# Galaksija_keyboard_matrix.net
KiCad netlist of a schematic drawn in EAGLE
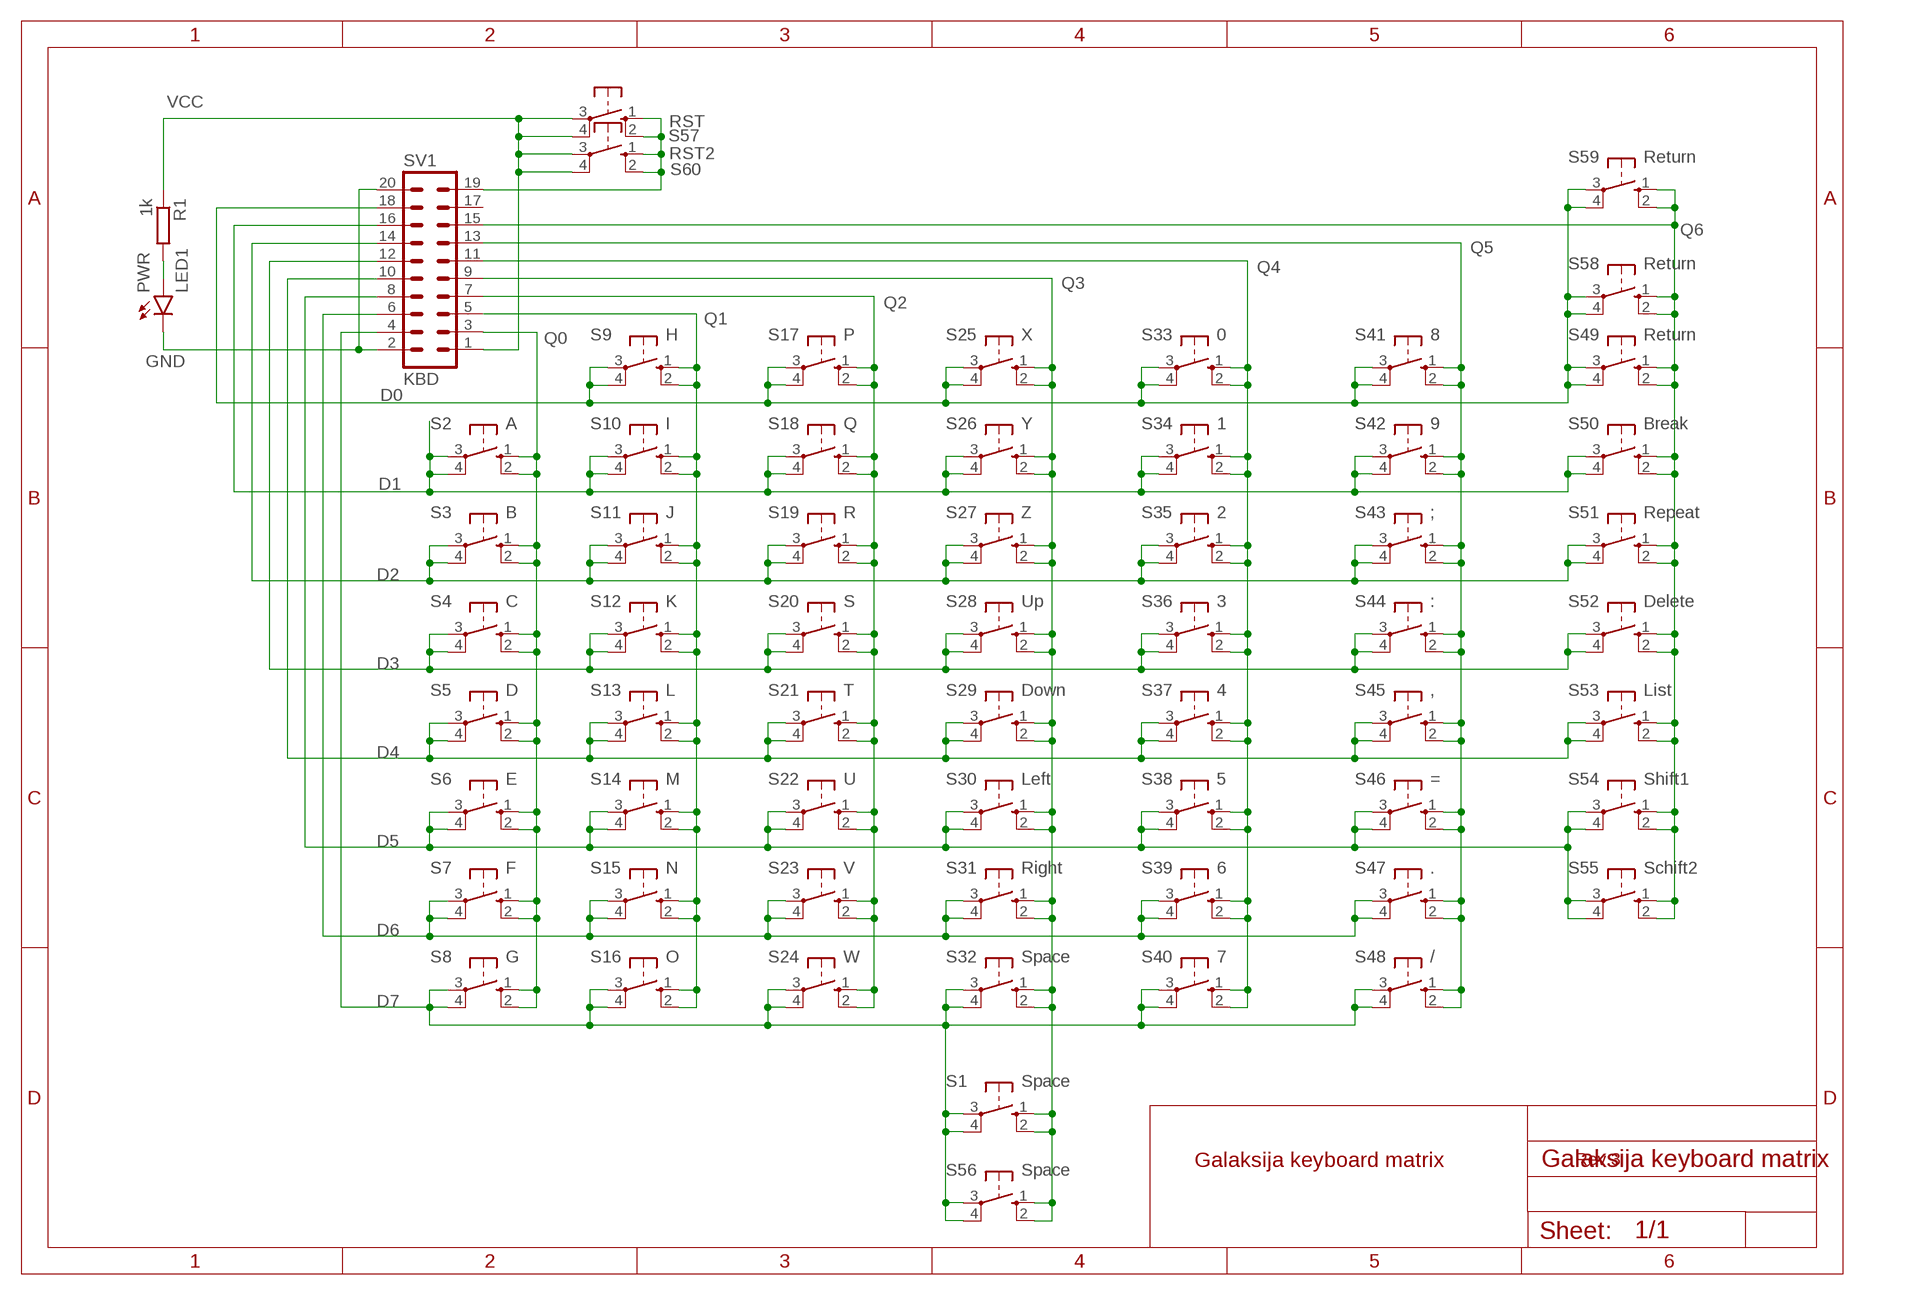
[diagram p0: schematic, sheet 1]

(export (version "E")
  (design (tool "Eeschema 10.0.6"))
  (components
    (comp (ref "LED1")
      (value "PWR")
      (footprint "eagle-import:LED5MM")
      (libsource (lib "eagle-import") (part "LED5MM"))
    )
    (comp (ref "R1")
      (value "1k")
      (footprint "eagle-import:0207_10")
      (libsource (lib "eagle-import") (part "R-EU_0207/10"))
    )
    (comp (ref "S1")
      (value "Space")
      (footprint "eagle-import:B3F-40XX")
      (fields (field (name "MF") "OMRON COMPONENTS USA") (field (name "MPN") "B3F-4000"))
      (libsource (lib "eagle-import") (part "40-XX"))
    )
    (comp (ref "S2")
      (value "A")
      (footprint "eagle-import:B3F-40XX")
      (fields (field (name "MF") "OMRON COMPONENTS USA") (field (name "MPN") "B3F-4000"))
      (libsource (lib "eagle-import") (part "40-XX"))
    )
    (comp (ref "S3")
      (value "B")
      (footprint "eagle-import:B3F-40XX")
      (fields (field (name "MF") "OMRON COMPONENTS USA") (field (name "MPN") "B3F-4000"))
      (libsource (lib "eagle-import") (part "40-XX"))
    )
    (comp (ref "S4")
      (value "C")
      (footprint "eagle-import:B3F-40XX")
      (fields (field (name "MF") "OMRON COMPONENTS USA") (field (name "MPN") "B3F-4000"))
      (libsource (lib "eagle-import") (part "40-XX"))
    )
    (comp (ref "S5")
      (value "D")
      (footprint "eagle-import:B3F-40XX")
      (fields (field (name "MF") "OMRON COMPONENTS USA") (field (name "MPN") "B3F-4000"))
      (libsource (lib "eagle-import") (part "40-XX"))
    )
    (comp (ref "S6")
      (value "E")
      (footprint "eagle-import:B3F-40XX")
      (fields (field (name "MF") "OMRON COMPONENTS USA") (field (name "MPN") "B3F-4000"))
      (libsource (lib "eagle-import") (part "40-XX"))
    )
    (comp (ref "S7")
      (value "F")
      (footprint "eagle-import:B3F-40XX")
      (fields (field (name "MF") "OMRON COMPONENTS USA") (field (name "MPN") "B3F-4000"))
      (libsource (lib "eagle-import") (part "40-XX"))
    )
    (comp (ref "S8")
      (value "G")
      (footprint "eagle-import:B3F-40XX")
      (fields (field (name "MF") "OMRON COMPONENTS USA") (field (name "MPN") "B3F-4000"))
      (libsource (lib "eagle-import") (part "40-XX"))
    )
    (comp (ref "S9")
      (value "H")
      (footprint "eagle-import:B3F-40XX")
      (fields (field (name "MF") "OMRON COMPONENTS USA") (field (name "MPN") "B3F-4000"))
      (libsource (lib "eagle-import") (part "40-XX"))
    )
    (comp (ref "S10")
      (value "I")
      (footprint "eagle-import:B3F-40XX")
      (fields (field (name "MF") "OMRON COMPONENTS USA") (field (name "MPN") "B3F-4000"))
      (libsource (lib "eagle-import") (part "40-XX"))
    )
    (comp (ref "S11")
      (value "J")
      (footprint "eagle-import:B3F-40XX")
      (fields (field (name "MF") "OMRON COMPONENTS USA") (field (name "MPN") "B3F-4000"))
      (libsource (lib "eagle-import") (part "40-XX"))
    )
    (comp (ref "S12")
      (value "K")
      (footprint "eagle-import:B3F-40XX")
      (fields (field (name "MF") "OMRON COMPONENTS USA") (field (name "MPN") "B3F-4000"))
      (libsource (lib "eagle-import") (part "40-XX"))
    )
    (comp (ref "S13")
      (value "L")
      (footprint "eagle-import:B3F-40XX")
      (fields (field (name "MF") "OMRON COMPONENTS USA") (field (name "MPN") "B3F-4000"))
      (libsource (lib "eagle-import") (part "40-XX"))
    )
    (comp (ref "S14")
      (value "M")
      (footprint "eagle-import:B3F-40XX")
      (fields (field (name "MF") "OMRON COMPONENTS USA") (field (name "MPN") "B3F-4000"))
      (libsource (lib "eagle-import") (part "40-XX"))
    )
    (comp (ref "S15")
      (value "N")
      (footprint "eagle-import:B3F-40XX")
      (fields (field (name "MF") "OMRON COMPONENTS USA") (field (name "MPN") "B3F-4000"))
      (libsource (lib "eagle-import") (part "40-XX"))
    )
    (comp (ref "S16")
      (value "O")
      (footprint "eagle-import:B3F-40XX")
      (fields (field (name "MF") "OMRON COMPONENTS USA") (field (name "MPN") "B3F-4000"))
      (libsource (lib "eagle-import") (part "40-XX"))
    )
    (comp (ref "S17")
      (value "P")
      (footprint "eagle-import:B3F-40XX")
      (fields (field (name "MF") "OMRON COMPONENTS USA") (field (name "MPN") "B3F-4000"))
      (libsource (lib "eagle-import") (part "40-XX"))
    )
    (comp (ref "S18")
      (value "Q")
      (footprint "eagle-import:B3F-40XX")
      (fields (field (name "MF") "OMRON COMPONENTS USA") (field (name "MPN") "B3F-4000"))
      (libsource (lib "eagle-import") (part "40-XX"))
    )
    (comp (ref "S19")
      (value "R")
      (footprint "eagle-import:B3F-40XX")
      (fields (field (name "MF") "OMRON COMPONENTS USA") (field (name "MPN") "B3F-4000"))
      (libsource (lib "eagle-import") (part "40-XX"))
    )
    (comp (ref "S20")
      (value "S")
      (footprint "eagle-import:B3F-40XX")
      (fields (field (name "MF") "OMRON COMPONENTS USA") (field (name "MPN") "B3F-4000"))
      (libsource (lib "eagle-import") (part "40-XX"))
    )
    (comp (ref "S21")
      (value "T")
      (footprint "eagle-import:B3F-40XX")
      (fields (field (name "MF") "OMRON COMPONENTS USA") (field (name "MPN") "B3F-4000"))
      (libsource (lib "eagle-import") (part "40-XX"))
    )
    (comp (ref "S22")
      (value "U")
      (footprint "eagle-import:B3F-40XX")
      (fields (field (name "MF") "OMRON COMPONENTS USA") (field (name "MPN") "B3F-4000"))
      (libsource (lib "eagle-import") (part "40-XX"))
    )
    (comp (ref "S23")
      (value "V")
      (footprint "eagle-import:B3F-40XX")
      (fields (field (name "MF") "OMRON COMPONENTS USA") (field (name "MPN") "B3F-4000"))
      (libsource (lib "eagle-import") (part "40-XX"))
    )
    (comp (ref "S24")
      (value "W")
      (footprint "eagle-import:B3F-40XX")
      (fields (field (name "MF") "OMRON COMPONENTS USA") (field (name "MPN") "B3F-4000"))
      (libsource (lib "eagle-import") (part "40-XX"))
    )
    (comp (ref "S25")
      (value "X")
      (footprint "eagle-import:B3F-40XX")
      (fields (field (name "MF") "OMRON COMPONENTS USA") (field (name "MPN") "B3F-4000"))
      (libsource (lib "eagle-import") (part "40-XX"))
    )
    (comp (ref "S26")
      (value "Y")
      (footprint "eagle-import:B3F-40XX")
      (fields (field (name "MF") "OMRON COMPONENTS USA") (field (name "MPN") "B3F-4000"))
      (libsource (lib "eagle-import") (part "40-XX"))
    )
    (comp (ref "S27")
      (value "Z")
      (footprint "eagle-import:B3F-40XX")
      (fields (field (name "MF") "OMRON COMPONENTS USA") (field (name "MPN") "B3F-4000"))
      (libsource (lib "eagle-import") (part "40-XX"))
    )
    (comp (ref "S28")
      (value "Up")
      (footprint "eagle-import:B3F-40XX")
      (fields (field (name "MF") "OMRON COMPONENTS USA") (field (name "MPN") "B3F-4000"))
      (libsource (lib "eagle-import") (part "40-XX"))
    )
    (comp (ref "S29")
      (value "Down")
      (footprint "eagle-import:B3F-40XX")
      (fields (field (name "MF") "OMRON COMPONENTS USA") (field (name "MPN") "B3F-4000"))
      (libsource (lib "eagle-import") (part "40-XX"))
    )
    (comp (ref "S30")
      (value "Left")
      (footprint "eagle-import:B3F-40XX")
      (fields (field (name "MF") "OMRON COMPONENTS USA") (field (name "MPN") "B3F-4000"))
      (libsource (lib "eagle-import") (part "40-XX"))
    )
    (comp (ref "S31")
      (value "Right")
      (footprint "eagle-import:B3F-40XX")
      (fields (field (name "MF") "OMRON COMPONENTS USA") (field (name "MPN") "B3F-4000"))
      (libsource (lib "eagle-import") (part "40-XX"))
    )
    (comp (ref "S32")
      (value "Space")
      (footprint "eagle-import:B3F-40XX")
      (fields (field (name "MF") "OMRON COMPONENTS USA") (field (name "MPN") "B3F-4000"))
      (libsource (lib "eagle-import") (part "40-XX"))
    )
    (comp (ref "S33")
      (value "0")
      (footprint "eagle-import:B3F-40XX")
      (fields (field (name "MF") "OMRON COMPONENTS USA") (field (name "MPN") "B3F-4000"))
      (libsource (lib "eagle-import") (part "40-XX"))
    )
    (comp (ref "S34")
      (value "1")
      (footprint "eagle-import:B3F-40XX")
      (fields (field (name "MF") "OMRON COMPONENTS USA") (field (name "MPN") "B3F-4000"))
      (libsource (lib "eagle-import") (part "40-XX"))
    )
    (comp (ref "S35")
      (value "2")
      (footprint "eagle-import:B3F-40XX")
      (fields (field (name "MF") "OMRON COMPONENTS USA") (field (name "MPN") "B3F-4000"))
      (libsource (lib "eagle-import") (part "40-XX"))
    )
    (comp (ref "S36")
      (value "3")
      (footprint "eagle-import:B3F-40XX")
      (fields (field (name "MF") "OMRON COMPONENTS USA") (field (name "MPN") "B3F-4000"))
      (libsource (lib "eagle-import") (part "40-XX"))
    )
    (comp (ref "S37")
      (value "4")
      (footprint "eagle-import:B3F-40XX")
      (fields (field (name "MF") "OMRON COMPONENTS USA") (field (name "MPN") "B3F-4000"))
      (libsource (lib "eagle-import") (part "40-XX"))
    )
    (comp (ref "S38")
      (value "5")
      (footprint "eagle-import:B3F-40XX")
      (fields (field (name "MF") "OMRON COMPONENTS USA") (field (name "MPN") "B3F-4000"))
      (libsource (lib "eagle-import") (part "40-XX"))
    )
    (comp (ref "S39")
      (value "6")
      (footprint "eagle-import:B3F-40XX")
      (fields (field (name "MF") "OMRON COMPONENTS USA") (field (name "MPN") "B3F-4000"))
      (libsource (lib "eagle-import") (part "40-XX"))
    )
    (comp (ref "S40")
      (value "7")
      (footprint "eagle-import:B3F-40XX")
      (fields (field (name "MF") "OMRON COMPONENTS USA") (field (name "MPN") "B3F-4000"))
      (libsource (lib "eagle-import") (part "40-XX"))
    )
    (comp (ref "S41")
      (value "8")
      (footprint "eagle-import:B3F-40XX")
      (fields (field (name "MF") "OMRON COMPONENTS USA") (field (name "MPN") "B3F-4000"))
      (libsource (lib "eagle-import") (part "40-XX"))
    )
    (comp (ref "S42")
      (value "9")
      (footprint "eagle-import:B3F-40XX")
      (fields (field (name "MF") "OMRON COMPONENTS USA") (field (name "MPN") "B3F-4000"))
      (libsource (lib "eagle-import") (part "40-XX"))
    )
    (comp (ref "S43")
      (value ";")
      (footprint "eagle-import:B3F-40XX")
      (fields (field (name "MF") "OMRON COMPONENTS USA") (field (name "MPN") "B3F-4000"))
      (libsource (lib "eagle-import") (part "40-XX"))
    )
    (comp (ref "S44")
      (value ":")
      (footprint "eagle-import:B3F-40XX")
      (fields (field (name "MF") "OMRON COMPONENTS USA") (field (name "MPN") "B3F-4000"))
      (libsource (lib "eagle-import") (part "40-XX"))
    )
    (comp (ref "S45")
      (value ",")
      (footprint "eagle-import:B3F-40XX")
      (fields (field (name "MF") "OMRON COMPONENTS USA") (field (name "MPN") "B3F-4000"))
      (libsource (lib "eagle-import") (part "40-XX"))
    )
    (comp (ref "S46")
      (value "=")
      (footprint "eagle-import:B3F-40XX")
      (fields (field (name "MF") "OMRON COMPONENTS USA") (field (name "MPN") "B3F-4000"))
      (libsource (lib "eagle-import") (part "40-XX"))
    )
    (comp (ref "S47")
      (value ".")
      (footprint "eagle-import:B3F-40XX")
      (fields (field (name "MF") "OMRON COMPONENTS USA") (field (name "MPN") "B3F-4000"))
      (libsource (lib "eagle-import") (part "40-XX"))
    )
    (comp (ref "S48")
      (value "/")
      (footprint "eagle-import:B3F-40XX")
      (fields (field (name "MF") "OMRON COMPONENTS USA") (field (name "MPN") "B3F-4000"))
      (libsource (lib "eagle-import") (part "40-XX"))
    )
    (comp (ref "S49")
      (value "Return")
      (footprint "eagle-import:B3F-40XX")
      (fields (field (name "MF") "OMRON COMPONENTS USA") (field (name "MPN") "B3F-4000"))
      (libsource (lib "eagle-import") (part "40-XX"))
    )
    (comp (ref "S50")
      (value "Break")
      (footprint "eagle-import:B3F-40XX")
      (fields (field (name "MF") "OMRON COMPONENTS USA") (field (name "MPN") "B3F-4000"))
      (libsource (lib "eagle-import") (part "40-XX"))
    )
    (comp (ref "S51")
      (value "Repeat")
      (footprint "eagle-import:B3F-40XX")
      (fields (field (name "MF") "OMRON COMPONENTS USA") (field (name "MPN") "B3F-4000"))
      (libsource (lib "eagle-import") (part "40-XX"))
    )
    (comp (ref "S52")
      (value "Delete")
      (footprint "eagle-import:B3F-40XX")
      (fields (field (name "MF") "OMRON COMPONENTS USA") (field (name "MPN") "B3F-4000"))
      (libsource (lib "eagle-import") (part "40-XX"))
    )
    (comp (ref "S53")
      (value "List")
      (footprint "eagle-import:B3F-40XX")
      (fields (field (name "MF") "OMRON COMPONENTS USA") (field (name "MPN") "B3F-4000"))
      (libsource (lib "eagle-import") (part "40-XX"))
    )
    (comp (ref "S54")
      (value "Shift1")
      (footprint "eagle-import:B3F-40XX")
      (fields (field (name "MF") "OMRON COMPONENTS USA") (field (name "MPN") "B3F-4000"))
      (libsource (lib "eagle-import") (part "40-XX"))
    )
    (comp (ref "S55")
      (value "Schift2")
      (footprint "eagle-import:B3F-40XX")
      (fields (field (name "MF") "OMRON COMPONENTS USA") (field (name "MPN") "B3F-4000"))
      (libsource (lib "eagle-import") (part "40-XX"))
    )
    (comp (ref "S56")
      (value "Space")
      (footprint "eagle-import:B3F-40XX")
      (fields (field (name "MF") "OMRON COMPONENTS USA") (field (name "MPN") "B3F-4000"))
      (libsource (lib "eagle-import") (part "40-XX"))
    )
    (comp (ref "S57")
      (value "RST")
      (footprint "eagle-import:B3F-40XX")
      (fields (field (name "MF") "OMRON COMPONENTS USA") (field (name "MPN") "B3F-4000"))
      (libsource (lib "eagle-import") (part "40-XX"))
    )
    (comp (ref "S58")
      (value "Return")
      (footprint "eagle-import:B3F-40XX")
      (fields (field (name "MF") "OMRON COMPONENTS USA") (field (name "MPN") "B3F-4000"))
      (libsource (lib "eagle-import") (part "40-XX"))
    )
    (comp (ref "S59")
      (value "Return")
      (footprint "eagle-import:B3F-40XX")
      (fields (field (name "MF") "OMRON COMPONENTS USA") (field (name "MPN") "B3F-4000"))
      (libsource (lib "eagle-import") (part "40-XX"))
    )
    (comp (ref "S60")
      (value "RST2")
      (footprint "eagle-import:B3F-10XX")
      (fields (field (name "MPN") "B3F-1000"))
      (libsource (lib "eagle-import") (part "10-XX"))
    )
    (comp (ref "SV1")
      (value "KBD")
      (footprint "eagle-import:ML20")
      (libsource (lib "eagle-import") (part "ML20"))
    )
  )
  (nets
    (net (code "1") (name "/D0") (class "Default")
      (node (ref "S17") (pin "3") (pinfunction "P_3") (pintype "passive"))
      (node (ref "S17") (pin "4") (pinfunction "P1_4") (pintype "passive"))
      (node (ref "S25") (pin "3") (pinfunction "P_3") (pintype "passive"))
      (node (ref "S25") (pin "4") (pinfunction "P1_4") (pintype "passive"))
      (node (ref "S33") (pin "3") (pinfunction "P_3") (pintype "passive"))
      (node (ref "S33") (pin "4") (pinfunction "P1_4") (pintype "passive"))
      (node (ref "S41") (pin "3") (pinfunction "P_3") (pintype "passive"))
      (node (ref "S41") (pin "4") (pinfunction "P1_4") (pintype "passive"))
      (node (ref "S49") (pin "3") (pinfunction "P_3") (pintype "passive"))
      (node (ref "S49") (pin "4") (pinfunction "P1_4") (pintype "passive"))
      (node (ref "S58") (pin "3") (pinfunction "P_3") (pintype "passive"))
      (node (ref "S58") (pin "4") (pinfunction "P1_4") (pintype "passive"))
      (node (ref "S59") (pin "3") (pinfunction "P_3") (pintype "passive"))
      (node (ref "S59") (pin "4") (pinfunction "P1_4") (pintype "passive"))
      (node (ref "S9") (pin "3") (pinfunction "P_3") (pintype "passive"))
      (node (ref "S9") (pin "4") (pinfunction "P1_4") (pintype "passive"))
      (node (ref "SV1") (pin "18") (pinfunction "18_18") (pintype "passive"))
    )
    (net (code "2") (name "/D1") (class "Default")
      (node (ref "S10") (pin "3") (pinfunction "P_3") (pintype "passive"))
      (node (ref "S10") (pin "4") (pinfunction "P1_4") (pintype "passive"))
      (node (ref "S18") (pin "3") (pinfunction "P_3") (pintype "passive"))
      (node (ref "S18") (pin "4") (pinfunction "P1_4") (pintype "passive"))
      (node (ref "S2") (pin "3") (pinfunction "P_3") (pintype "passive"))
      (node (ref "S2") (pin "4") (pinfunction "P1_4") (pintype "passive"))
      (node (ref "S26") (pin "3") (pinfunction "P_3") (pintype "passive"))
      (node (ref "S26") (pin "4") (pinfunction "P1_4") (pintype "passive"))
      (node (ref "S34") (pin "3") (pinfunction "P_3") (pintype "passive"))
      (node (ref "S34") (pin "4") (pinfunction "P1_4") (pintype "passive"))
      (node (ref "S42") (pin "3") (pinfunction "P_3") (pintype "passive"))
      (node (ref "S42") (pin "4") (pinfunction "P1_4") (pintype "passive"))
      (node (ref "S50") (pin "3") (pinfunction "P_3") (pintype "passive"))
      (node (ref "S50") (pin "4") (pinfunction "P1_4") (pintype "passive"))
      (node (ref "SV1") (pin "16") (pinfunction "16_16") (pintype "passive"))
    )
    (net (code "3") (name "/D2") (class "Default")
      (node (ref "S11") (pin "3") (pinfunction "P_3") (pintype "passive"))
      (node (ref "S11") (pin "4") (pinfunction "P1_4") (pintype "passive"))
      (node (ref "S19") (pin "3") (pinfunction "P_3") (pintype "passive"))
      (node (ref "S19") (pin "4") (pinfunction "P1_4") (pintype "passive"))
      (node (ref "S27") (pin "3") (pinfunction "P_3") (pintype "passive"))
      (node (ref "S27") (pin "4") (pinfunction "P1_4") (pintype "passive"))
      (node (ref "S3") (pin "3") (pinfunction "P_3") (pintype "passive"))
      (node (ref "S3") (pin "4") (pinfunction "P1_4") (pintype "passive"))
      (node (ref "S35") (pin "3") (pinfunction "P_3") (pintype "passive"))
      (node (ref "S35") (pin "4") (pinfunction "P1_4") (pintype "passive"))
      (node (ref "S43") (pin "3") (pinfunction "P_3") (pintype "passive"))
      (node (ref "S43") (pin "4") (pinfunction "P1_4") (pintype "passive"))
      (node (ref "S51") (pin "3") (pinfunction "P_3") (pintype "passive"))
      (node (ref "S51") (pin "4") (pinfunction "P1_4") (pintype "passive"))
      (node (ref "SV1") (pin "14") (pinfunction "14_14") (pintype "passive"))
    )
    (net (code "4") (name "/D3") (class "Default")
      (node (ref "S12") (pin "3") (pinfunction "P_3") (pintype "passive"))
      (node (ref "S12") (pin "4") (pinfunction "P1_4") (pintype "passive"))
      (node (ref "S20") (pin "3") (pinfunction "P_3") (pintype "passive"))
      (node (ref "S20") (pin "4") (pinfunction "P1_4") (pintype "passive"))
      (node (ref "S28") (pin "3") (pinfunction "P_3") (pintype "passive"))
      (node (ref "S28") (pin "4") (pinfunction "P1_4") (pintype "passive"))
      (node (ref "S36") (pin "3") (pinfunction "P_3") (pintype "passive"))
      (node (ref "S36") (pin "4") (pinfunction "P1_4") (pintype "passive"))
      (node (ref "S4") (pin "3") (pinfunction "P_3") (pintype "passive"))
      (node (ref "S4") (pin "4") (pinfunction "P1_4") (pintype "passive"))
      (node (ref "S44") (pin "3") (pinfunction "P_3") (pintype "passive"))
      (node (ref "S44") (pin "4") (pinfunction "P1_4") (pintype "passive"))
      (node (ref "S52") (pin "3") (pinfunction "P_3") (pintype "passive"))
      (node (ref "S52") (pin "4") (pinfunction "P1_4") (pintype "passive"))
      (node (ref "SV1") (pin "12") (pinfunction "12_12") (pintype "passive"))
    )
    (net (code "5") (name "/D4") (class "Default")
      (node (ref "S13") (pin "3") (pinfunction "P_3") (pintype "passive"))
      (node (ref "S13") (pin "4") (pinfunction "P1_4") (pintype "passive"))
      (node (ref "S21") (pin "3") (pinfunction "P_3") (pintype "passive"))
      (node (ref "S21") (pin "4") (pinfunction "P1_4") (pintype "passive"))
      (node (ref "S29") (pin "3") (pinfunction "P_3") (pintype "passive"))
      (node (ref "S29") (pin "4") (pinfunction "P1_4") (pintype "passive"))
      (node (ref "S37") (pin "3") (pinfunction "P_3") (pintype "passive"))
      (node (ref "S37") (pin "4") (pinfunction "P1_4") (pintype "passive"))
      (node (ref "S45") (pin "3") (pinfunction "P_3") (pintype "passive"))
      (node (ref "S45") (pin "4") (pinfunction "P1_4") (pintype "passive"))
      (node (ref "S5") (pin "3") (pinfunction "P_3") (pintype "passive"))
      (node (ref "S5") (pin "4") (pinfunction "P1_4") (pintype "passive"))
      (node (ref "S53") (pin "3") (pinfunction "P_3") (pintype "passive"))
      (node (ref "S53") (pin "4") (pinfunction "P1_4") (pintype "passive"))
      (node (ref "SV1") (pin "10") (pinfunction "10_10") (pintype "passive"))
    )
    (net (code "6") (name "/D5") (class "Default")
      (node (ref "S14") (pin "3") (pinfunction "P_3") (pintype "passive"))
      (node (ref "S14") (pin "4") (pinfunction "P1_4") (pintype "passive"))
      (node (ref "S22") (pin "3") (pinfunction "P_3") (pintype "passive"))
      (node (ref "S22") (pin "4") (pinfunction "P1_4") (pintype "passive"))
      (node (ref "S30") (pin "3") (pinfunction "P_3") (pintype "passive"))
      (node (ref "S30") (pin "4") (pinfunction "P1_4") (pintype "passive"))
      (node (ref "S38") (pin "3") (pinfunction "P_3") (pintype "passive"))
      (node (ref "S38") (pin "4") (pinfunction "P1_4") (pintype "passive"))
      (node (ref "S46") (pin "3") (pinfunction "P_3") (pintype "passive"))
      (node (ref "S46") (pin "4") (pinfunction "P1_4") (pintype "passive"))
      (node (ref "S54") (pin "3") (pinfunction "P_3") (pintype "passive"))
      (node (ref "S54") (pin "4") (pinfunction "P1_4") (pintype "passive"))
      (node (ref "S55") (pin "3") (pinfunction "P_3") (pintype "passive"))
      (node (ref "S55") (pin "4") (pinfunction "P1_4") (pintype "passive"))
      (node (ref "S6") (pin "3") (pinfunction "P_3") (pintype "passive"))
      (node (ref "S6") (pin "4") (pinfunction "P1_4") (pintype "passive"))
      (node (ref "SV1") (pin "8") (pinfunction "8_8") (pintype "passive"))
    )
    (net (code "7") (name "/D6") (class "Default")
      (node (ref "S15") (pin "3") (pinfunction "P_3") (pintype "passive"))
      (node (ref "S15") (pin "4") (pinfunction "P1_4") (pintype "passive"))
      (node (ref "S23") (pin "3") (pinfunction "P_3") (pintype "passive"))
      (node (ref "S23") (pin "4") (pinfunction "P1_4") (pintype "passive"))
      (node (ref "S31") (pin "3") (pinfunction "P_3") (pintype "passive"))
      (node (ref "S31") (pin "4") (pinfunction "P1_4") (pintype "passive"))
      (node (ref "S39") (pin "3") (pinfunction "P_3") (pintype "passive"))
      (node (ref "S39") (pin "4") (pinfunction "P1_4") (pintype "passive"))
      (node (ref "S47") (pin "3") (pinfunction "P_3") (pintype "passive"))
      (node (ref "S47") (pin "4") (pinfunction "P1_4") (pintype "passive"))
      (node (ref "S7") (pin "3") (pinfunction "P_3") (pintype "passive"))
      (node (ref "S7") (pin "4") (pinfunction "P1_4") (pintype "passive"))
      (node (ref "SV1") (pin "6") (pinfunction "6_6") (pintype "passive"))
    )
    (net (code "8") (name "/D7") (class "Default")
      (node (ref "S1") (pin "3") (pinfunction "P_3") (pintype "passive"))
      (node (ref "S1") (pin "4") (pinfunction "P1_4") (pintype "passive"))
      (node (ref "S16") (pin "3") (pinfunction "P_3") (pintype "passive"))
      (node (ref "S16") (pin "4") (pinfunction "P1_4") (pintype "passive"))
      (node (ref "S24") (pin "3") (pinfunction "P_3") (pintype "passive"))
      (node (ref "S24") (pin "4") (pinfunction "P1_4") (pintype "passive"))
      (node (ref "S32") (pin "3") (pinfunction "P_3") (pintype "passive"))
      (node (ref "S32") (pin "4") (pinfunction "P1_4") (pintype "passive"))
      (node (ref "S40") (pin "3") (pinfunction "P_3") (pintype "passive"))
      (node (ref "S40") (pin "4") (pinfunction "P1_4") (pintype "passive"))
      (node (ref "S48") (pin "3") (pinfunction "P_3") (pintype "passive"))
      (node (ref "S48") (pin "4") (pinfunction "P1_4") (pintype "passive"))
      (node (ref "S56") (pin "3") (pinfunction "P_3") (pintype "passive"))
      (node (ref "S56") (pin "4") (pinfunction "P1_4") (pintype "passive"))
      (node (ref "S8") (pin "3") (pinfunction "P_3") (pintype "passive"))
      (node (ref "S8") (pin "4") (pinfunction "P1_4") (pintype "passive"))
      (node (ref "SV1") (pin "4") (pinfunction "4_4") (pintype "passive"))
    )
    (net (code "9") (name "/GND") (class "Default")
      (node (ref "LED1") (pin "K") (pinfunction "C_K") (pintype "passive"))
      (node (ref "SV1") (pin "2") (pinfunction "2_2") (pintype "passive"))
      (node (ref "SV1") (pin "20") (pinfunction "20_20") (pintype "passive"))
    )
    (net (code "10") (name "/Q0") (class "Default")
      (node (ref "S2") (pin "1") (pinfunction "S_1") (pintype "passive"))
      (node (ref "S2") (pin "2") (pinfunction "S1_2") (pintype "passive"))
      (node (ref "S3") (pin "1") (pinfunction "S_1") (pintype "passive"))
      (node (ref "S3") (pin "2") (pinfunction "S1_2") (pintype "passive"))
      (node (ref "S4") (pin "1") (pinfunction "S_1") (pintype "passive"))
      (node (ref "S4") (pin "2") (pinfunction "S1_2") (pintype "passive"))
      (node (ref "S5") (pin "1") (pinfunction "S_1") (pintype "passive"))
      (node (ref "S5") (pin "2") (pinfunction "S1_2") (pintype "passive"))
      (node (ref "S6") (pin "1") (pinfunction "S_1") (pintype "passive"))
      (node (ref "S6") (pin "2") (pinfunction "S1_2") (pintype "passive"))
      (node (ref "S7") (pin "1") (pinfunction "S_1") (pintype "passive"))
      (node (ref "S7") (pin "2") (pinfunction "S1_2") (pintype "passive"))
      (node (ref "S8") (pin "1") (pinfunction "S_1") (pintype "passive"))
      (node (ref "S8") (pin "2") (pinfunction "S1_2") (pintype "passive"))
      (node (ref "SV1") (pin "3") (pinfunction "3_3") (pintype "passive"))
    )
    (net (code "11") (name "/Q1") (class "Default")
      (node (ref "S10") (pin "1") (pinfunction "S_1") (pintype "passive"))
      (node (ref "S10") (pin "2") (pinfunction "S1_2") (pintype "passive"))
      (node (ref "S11") (pin "1") (pinfunction "S_1") (pintype "passive"))
      (node (ref "S11") (pin "2") (pinfunction "S1_2") (pintype "passive"))
      (node (ref "S12") (pin "1") (pinfunction "S_1") (pintype "passive"))
      (node (ref "S12") (pin "2") (pinfunction "S1_2") (pintype "passive"))
      (node (ref "S13") (pin "1") (pinfunction "S_1") (pintype "passive"))
      (node (ref "S13") (pin "2") (pinfunction "S1_2") (pintype "passive"))
      (node (ref "S14") (pin "1") (pinfunction "S_1") (pintype "passive"))
      (node (ref "S14") (pin "2") (pinfunction "S1_2") (pintype "passive"))
      (node (ref "S15") (pin "1") (pinfunction "S_1") (pintype "passive"))
      (node (ref "S15") (pin "2") (pinfunction "S1_2") (pintype "passive"))
      (node (ref "S16") (pin "1") (pinfunction "S_1") (pintype "passive"))
      (node (ref "S16") (pin "2") (pinfunction "S1_2") (pintype "passive"))
      (node (ref "S9") (pin "1") (pinfunction "S_1") (pintype "passive"))
      (node (ref "S9") (pin "2") (pinfunction "S1_2") (pintype "passive"))
      (node (ref "SV1") (pin "5") (pinfunction "5_5") (pintype "passive"))
    )
    (net (code "12") (name "/Q2") (class "Default")
      (node (ref "S17") (pin "1") (pinfunction "S_1") (pintype "passive"))
      (node (ref "S17") (pin "2") (pinfunction "S1_2") (pintype "passive"))
      (node (ref "S18") (pin "1") (pinfunction "S_1") (pintype "passive"))
      (node (ref "S18") (pin "2") (pinfunction "S1_2") (pintype "passive"))
      (node (ref "S19") (pin "1") (pinfunction "S_1") (pintype "passive"))
      (node (ref "S19") (pin "2") (pinfunction "S1_2") (pintype "passive"))
      (node (ref "S20") (pin "1") (pinfunction "S_1") (pintype "passive"))
      (node (ref "S20") (pin "2") (pinfunction "S1_2") (pintype "passive"))
      (node (ref "S21") (pin "1") (pinfunction "S_1") (pintype "passive"))
      (node (ref "S21") (pin "2") (pinfunction "S1_2") (pintype "passive"))
      (node (ref "S22") (pin "1") (pinfunction "S_1") (pintype "passive"))
      (node (ref "S22") (pin "2") (pinfunction "S1_2") (pintype "passive"))
      (node (ref "S23") (pin "1") (pinfunction "S_1") (pintype "passive"))
      (node (ref "S23") (pin "2") (pinfunction "S1_2") (pintype "passive"))
      (node (ref "S24") (pin "1") (pinfunction "S_1") (pintype "passive"))
      (node (ref "S24") (pin "2") (pinfunction "S1_2") (pintype "passive"))
      (node (ref "SV1") (pin "7") (pinfunction "7_7") (pintype "passive"))
    )
    (net (code "13") (name "/Q3") (class "Default")
      (node (ref "S1") (pin "1") (pinfunction "S_1") (pintype "passive"))
      (node (ref "S1") (pin "2") (pinfunction "S1_2") (pintype "passive"))
      (node (ref "S25") (pin "1") (pinfunction "S_1") (pintype "passive"))
      (node (ref "S25") (pin "2") (pinfunction "S1_2") (pintype "passive"))
      (node (ref "S26") (pin "1") (pinfunction "S_1") (pintype "passive"))
      (node (ref "S26") (pin "2") (pinfunction "S1_2") (pintype "passive"))
      (node (ref "S27") (pin "1") (pinfunction "S_1") (pintype "passive"))
      (node (ref "S27") (pin "2") (pinfunction "S1_2") (pintype "passive"))
      (node (ref "S28") (pin "1") (pinfunction "S_1") (pintype "passive"))
      (node (ref "S28") (pin "2") (pinfunction "S1_2") (pintype "passive"))
      (node (ref "S29") (pin "1") (pinfunction "S_1") (pintype "passive"))
      (node (ref "S29") (pin "2") (pinfunction "S1_2") (pintype "passive"))
      (node (ref "S30") (pin "1") (pinfunction "S_1") (pintype "passive"))
      (node (ref "S30") (pin "2") (pinfunction "S1_2") (pintype "passive"))
      (node (ref "S31") (pin "1") (pinfunction "S_1") (pintype "passive"))
      (node (ref "S31") (pin "2") (pinfunction "S1_2") (pintype "passive"))
      (node (ref "S32") (pin "1") (pinfunction "S_1") (pintype "passive"))
      (node (ref "S32") (pin "2") (pinfunction "S1_2") (pintype "passive"))
      (node (ref "S56") (pin "1") (pinfunction "S_1") (pintype "passive"))
      (node (ref "S56") (pin "2") (pinfunction "S1_2") (pintype "passive"))
      (node (ref "SV1") (pin "9") (pinfunction "9_9") (pintype "passive"))
    )
    (net (code "14") (name "/Q4") (class "Default")
      (node (ref "S33") (pin "1") (pinfunction "S_1") (pintype "passive"))
      (node (ref "S33") (pin "2") (pinfunction "S1_2") (pintype "passive"))
      (node (ref "S34") (pin "1") (pinfunction "S_1") (pintype "passive"))
      (node (ref "S34") (pin "2") (pinfunction "S1_2") (pintype "passive"))
      (node (ref "S35") (pin "1") (pinfunction "S_1") (pintype "passive"))
      (node (ref "S35") (pin "2") (pinfunction "S1_2") (pintype "passive"))
      (node (ref "S36") (pin "1") (pinfunction "S_1") (pintype "passive"))
      (node (ref "S36") (pin "2") (pinfunction "S1_2") (pintype "passive"))
      (node (ref "S37") (pin "1") (pinfunction "S_1") (pintype "passive"))
      (node (ref "S37") (pin "2") (pinfunction "S1_2") (pintype "passive"))
      (node (ref "S38") (pin "1") (pinfunction "S_1") (pintype "passive"))
      (node (ref "S38") (pin "2") (pinfunction "S1_2") (pintype "passive"))
      (node (ref "S39") (pin "1") (pinfunction "S_1") (pintype "passive"))
      (node (ref "S39") (pin "2") (pinfunction "S1_2") (pintype "passive"))
      (node (ref "S40") (pin "1") (pinfunction "S_1") (pintype "passive"))
      (node (ref "S40") (pin "2") (pinfunction "S1_2") (pintype "passive"))
      (node (ref "SV1") (pin "11") (pinfunction "11_11") (pintype "passive"))
    )
    (net (code "15") (name "/Q5") (class "Default")
      (node (ref "S41") (pin "1") (pinfunction "S_1") (pintype "passive"))
      (node (ref "S41") (pin "2") (pinfunction "S1_2") (pintype "passive"))
      (node (ref "S42") (pin "1") (pinfunction "S_1") (pintype "passive"))
      (node (ref "S42") (pin "2") (pinfunction "S1_2") (pintype "passive"))
      (node (ref "S43") (pin "1") (pinfunction "S_1") (pintype "passive"))
      (node (ref "S43") (pin "2") (pinfunction "S1_2") (pintype "passive"))
      (node (ref "S44") (pin "1") (pinfunction "S_1") (pintype "passive"))
      (node (ref "S44") (pin "2") (pinfunction "S1_2") (pintype "passive"))
      (node (ref "S45") (pin "1") (pinfunction "S_1") (pintype "passive"))
      (node (ref "S45") (pin "2") (pinfunction "S1_2") (pintype "passive"))
      (node (ref "S46") (pin "1") (pinfunction "S_1") (pintype "passive"))
      (node (ref "S46") (pin "2") (pinfunction "S1_2") (pintype "passive"))
      (node (ref "S47") (pin "1") (pinfunction "S_1") (pintype "passive"))
      (node (ref "S47") (pin "2") (pinfunction "S1_2") (pintype "passive"))
      (node (ref "S48") (pin "1") (pinfunction "S_1") (pintype "passive"))
      (node (ref "S48") (pin "2") (pinfunction "S1_2") (pintype "passive"))
      (node (ref "SV1") (pin "13") (pinfunction "13_13") (pintype "passive"))
    )
    (net (code "16") (name "/Q6") (class "Default")
      (node (ref "S49") (pin "1") (pinfunction "S_1") (pintype "passive"))
      (node (ref "S49") (pin "2") (pinfunction "S1_2") (pintype "passive"))
      (node (ref "S50") (pin "1") (pinfunction "S_1") (pintype "passive"))
      (node (ref "S50") (pin "2") (pinfunction "S1_2") (pintype "passive"))
      (node (ref "S51") (pin "1") (pinfunction "S_1") (pintype "passive"))
      (node (ref "S51") (pin "2") (pinfunction "S1_2") (pintype "passive"))
      (node (ref "S52") (pin "1") (pinfunction "S_1") (pintype "passive"))
      (node (ref "S52") (pin "2") (pinfunction "S1_2") (pintype "passive"))
      (node (ref "S53") (pin "1") (pinfunction "S_1") (pintype "passive"))
      (node (ref "S53") (pin "2") (pinfunction "S1_2") (pintype "passive"))
      (node (ref "S54") (pin "1") (pinfunction "S_1") (pintype "passive"))
      (node (ref "S54") (pin "2") (pinfunction "S1_2") (pintype "passive"))
      (node (ref "S55") (pin "1") (pinfunction "S_1") (pintype "passive"))
      (node (ref "S55") (pin "2") (pinfunction "S1_2") (pintype "passive"))
      (node (ref "S58") (pin "1") (pinfunction "S_1") (pintype "passive"))
      (node (ref "S58") (pin "2") (pinfunction "S1_2") (pintype "passive"))
      (node (ref "S59") (pin "1") (pinfunction "S_1") (pintype "passive"))
      (node (ref "S59") (pin "2") (pinfunction "S1_2") (pintype "passive"))
      (node (ref "SV1") (pin "15") (pinfunction "15_15") (pintype "passive"))
    )
    (net (code "17") (name "/VCC") (class "Default")
      (node (ref "R1") (pin "1") (pinfunction "1_1") (pintype "passive"))
      (node (ref "S57") (pin "3") (pinfunction "P_3") (pintype "passive"))
      (node (ref "S57") (pin "4") (pinfunction "P1_4") (pintype "passive"))
      (node (ref "S60") (pin "3") (pinfunction "P_3") (pintype "passive"))
      (node (ref "S60") (pin "4") (pinfunction "P1_4") (pintype "passive"))
      (node (ref "SV1") (pin "1") (pinfunction "1_1") (pintype "passive"))
    )
    (net (code "18") (name "Net-(LED1-PadA)") (class "Default")
      (node (ref "LED1") (pin "A") (pinfunction "A_A") (pintype "passive"))
      (node (ref "R1") (pin "2") (pinfunction "2_2") (pintype "passive"))
    )
    (net (code "19") (name "Net-(S57-S)") (class "Default")
      (node (ref "S57") (pin "1") (pinfunction "S_1") (pintype "passive"))
      (node (ref "S57") (pin "2") (pinfunction "S1_2") (pintype "passive"))
      (node (ref "S60") (pin "1") (pinfunction "S_1") (pintype "passive"))
      (node (ref "S60") (pin "2") (pinfunction "S1_2") (pintype "passive"))
      (node (ref "SV1") (pin "19") (pinfunction "19_19") (pintype "passive"))
    )
    (net (code "20") (name "unconnected-(SV1-Pad17)") (class "Default")
      (node (ref "SV1") (pin "17") (pinfunction "17_17") (pintype "passive"))
    )
  )
)
